# WL-AUDIO.net
KiCad netlist of a schematic drawn in Altium Designer
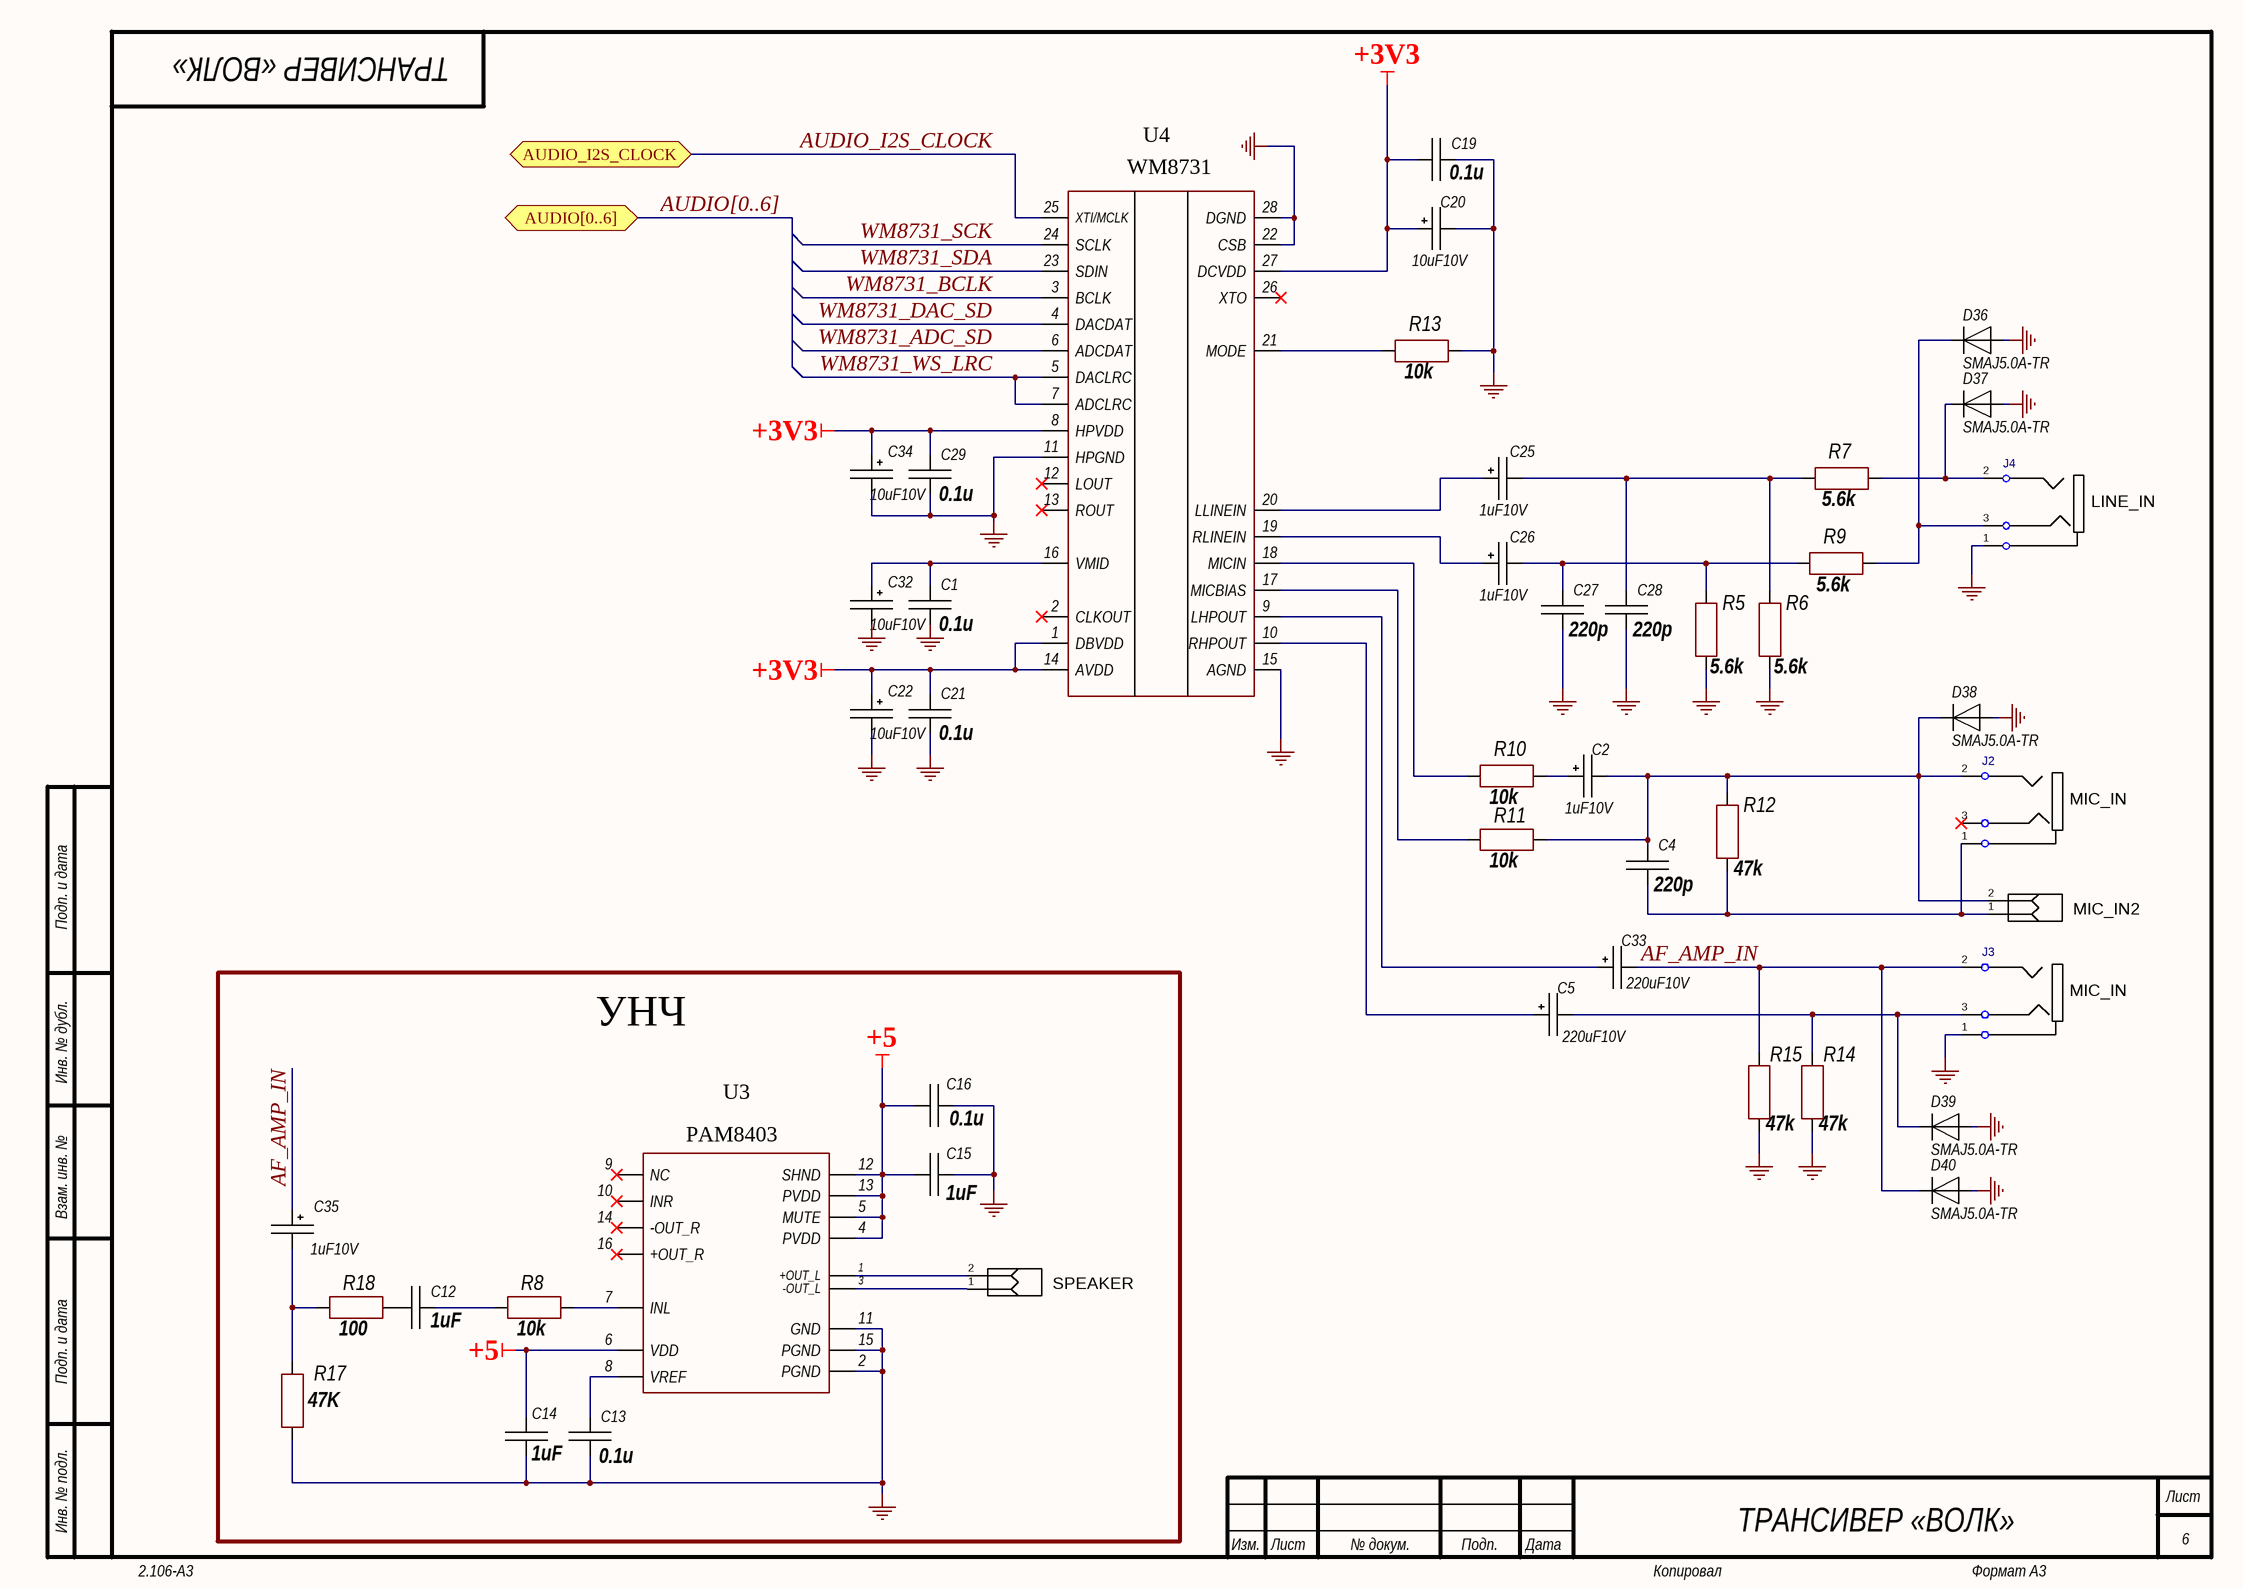
[diagram p0: WL-AUDIO.SchDoc]

(export (version "E")
  (design (tool "Eeschema 10.0.6"))
  (components
    (comp (ref "C1")
      (value "0.1u")
      (footprint "standard:CH0201C")
      (libsource (lib "Discrete") (part "Capacitor"))
    )
    (comp (ref "C2")
      (value "1uF10V")
      (footprint "standard:D5C2H11")
      (libsource (lib "Discrete") (part "AlumCap"))
    )
    (comp (ref "C4")
      (value "220p")
      (footprint "standard:CH0201C")
      (libsource (lib "Discrete") (part "Capacitor"))
    )
    (comp (ref "C5")
      (value "220uF10V")
      (footprint "standard:D5C2H11")
      (libsource (lib "Discrete") (part "AlumCap"))
    )
    (comp (ref "C12")
      (value "1uF")
      (footprint "standard:CH0201C")
      (libsource (lib "Discrete") (part "Capacitor"))
    )
    (comp (ref "C13")
      (value "0.1u")
      (footprint "standard:CH0805C")
      (libsource (lib "Discrete") (part "Capacitor"))
    )
    (comp (ref "C14")
      (value "1uF")
      (footprint "standard:CH0805C")
      (libsource (lib "Discrete") (part "Capacitor"))
    )
    (comp (ref "C15")
      (value "1uF")
      (footprint "standard:CH0805C")
      (libsource (lib "Discrete") (part "Capacitor"))
    )
    (comp (ref "C16")
      (value "0.1u")
      (footprint "standard:CH0805C")
      (libsource (lib "Discrete") (part "Capacitor"))
    )
    (comp (ref "C19")
      (value "0.1u")
      (footprint "standard:CH0201C")
      (libsource (lib "Discrete") (part "Capacitor"))
    )
    (comp (ref "C20")
      (value "10uF10V")
      (footprint "standard:D5C2H11")
      (libsource (lib "Discrete") (part "AlumCap"))
    )
    (comp (ref "C21")
      (value "0.1u")
      (footprint "standard:CH0201C")
      (libsource (lib "Discrete") (part "Capacitor"))
    )
    (comp (ref "C22")
      (value "10uF10V")
      (footprint "standard:D5C2H11")
      (libsource (lib "Discrete") (part "AlumCap"))
    )
    (comp (ref "C25")
      (value "1uF10V")
      (footprint "standard:D5C2H11")
      (libsource (lib "Discrete") (part "AlumCap"))
    )
    (comp (ref "C26")
      (value "1uF10V")
      (footprint "standard:D5C2H11")
      (libsource (lib "Discrete") (part "AlumCap"))
    )
    (comp (ref "C27")
      (value "220p")
      (footprint "standard:CH0201C")
      (libsource (lib "Discrete") (part "Capacitor"))
    )
    (comp (ref "C28")
      (value "220p")
      (footprint "standard:CH0201C")
      (libsource (lib "Discrete") (part "Capacitor"))
    )
    (comp (ref "C29")
      (value "0.1u")
      (footprint "standard:CH0201C")
      (libsource (lib "Discrete") (part "Capacitor"))
    )
    (comp (ref "C32")
      (value "10uF10V")
      (footprint "standard:D5C2H11")
      (libsource (lib "Discrete") (part "AlumCap"))
    )
    (comp (ref "C33")
      (value "220uF10V")
      (footprint "standard:D5C2H11")
      (libsource (lib "Discrete") (part "AlumCap"))
    )
    (comp (ref "C34")
      (value "10uF10V")
      (footprint "standard:D5C2H11")
      (libsource (lib "Discrete") (part "AlumCap"))
    )
    (comp (ref "C35")
      (value "1uF10V")
      (footprint "standard:D5C2H11")
      (libsource (lib "Discrete") (part "AlumCap"))
    )
    (comp (ref "D36")
      (value "SMAJ5.0A-TR")
      (footprint "standard:SOD123")
      (libsource (lib "Diods") (part "Diod"))
    )
    (comp (ref "D37")
      (value "SMAJ5.0A-TR")
      (footprint "standard:SOD123")
      (libsource (lib "Diods") (part "Diod"))
    )
    (comp (ref "D38")
      (value "SMAJ5.0A-TR")
      (footprint "standard:SOD123")
      (libsource (lib "Diods") (part "Diod"))
    )
    (comp (ref "D39")
      (value "SMAJ5.0A-TR")
      (footprint "standard:SOD123")
      (libsource (lib "Diods") (part "Diod"))
    )
    (comp (ref "D40")
      (value "SMAJ5.0A-TR")
      (footprint "standard:SOD123")
      (libsource (lib "Diods") (part "Diod"))
    )
    (comp (ref "J2")
      (value "MIC_IN")
      (footprint "SJ1-3525NG")
      (description "SJ1-3525NG")
      (libsource (lib "*") (part "SJ1-3523N"))
    )
    (comp (ref "J3")
      (value "MIC_IN")
      (footprint "SJ1-3525NG")
      (description "SJ1-3525NG")
      (libsource (lib "*") (part "SJ1-3523N"))
    )
    (comp (ref "J4")
      (value "LINE_IN")
      (footprint "SJ1-3525NG")
      (description "SJ1-3525NG")
      (libsource (lib "*") (part "SJ1-3523N"))
    )
    (comp (ref "MIС_IN2")
      (value "MIС_IN2")
      (footprint "51022-0200")
      (description "2 Pin")
      (libsource (lib "*") (part "51022-0200"))
    )
    (comp (ref "R5")
      (value "5.6k")
      (footprint "standard:CH0805R")
      (libsource (lib "Discrete") (part "Resistor"))
    )
    (comp (ref "R6")
      (value "5.6k")
      (footprint "standard:CH0805R")
      (libsource (lib "Discrete") (part "Resistor"))
    )
    (comp (ref "R7") (value "5.6k") (footprint "standard:CH0805R") (libsource (lib "") (part "Resistor_1")))
    (comp (ref "R8") (value "10k") (footprint "standard:CH0805R") (libsource (lib "") (part "Resistor_1")))
    (comp (ref "R9") (value "5.6k") (footprint "standard:CH0805R") (libsource (lib "") (part "Resistor_1")))
    (comp (ref "R10") (value "10k") (footprint "standard:CH0805R") (libsource (lib "") (part "Resistor_1")))
    (comp (ref "R11") (value "10k") (footprint "standard:CH0805R") (libsource (lib "") (part "Resistor_1")))
    (comp (ref "R12")
      (value "47k")
      (footprint "standard:CH0805R")
      (libsource (lib "Discrete") (part "Resistor"))
    )
    (comp (ref "R13") (value "10k") (footprint "standard:CH0805R") (libsource (lib "") (part "Resistor_1")))
    (comp (ref "R14")
      (value "47k")
      (footprint "standard:CH0805R")
      (libsource (lib "Discrete") (part "Resistor"))
    )
    (comp (ref "R15")
      (value "47k")
      (footprint "standard:CH0805R")
      (libsource (lib "Discrete") (part "Resistor"))
    )
    (comp (ref "R17")
      (value "47K")
      (footprint "standard:CH0805R")
      (libsource (lib "Discrete") (part "Resistor"))
    )
    (comp (ref "R18") (value "100") (footprint "standard:CH0805R") (libsource (lib "") (part "Resistor_1")))
    (comp (ref "SPEAKER")
      (value "MIС_IN2")
      (footprint "51022-0200")
      (description "2 Pin")
      (libsource (lib "*") (part "51022-0200"))
    )
    (comp (ref "U3") (value "PAM8403") (footprint "16-SOP") (libsource (lib "Digital") (part "PAM8403")))
    (comp (ref "U4") (value "WM8731") (footprint "28-SSOP") (libsource (lib "Digital") (part "WM8731")))
  )
  (nets
    (net (code "8") (name "+3V3") (class "Default")
      (node (ref "C19") (pin "1") (pinfunction "1_1") (pintype "power_in"))
      (node (ref "C20") (pin "1") (pinfunction "1_1") (pintype "power_in"))
      (node (ref "C21") (pin "2") (pinfunction "2_2") (pintype "power_in"))
      (node (ref "C22") (pin "1") (pinfunction "1_1") (pintype "power_in"))
      (node (ref "C29") (pin "2") (pinfunction "2_2") (pintype "power_in"))
      (node (ref "C34") (pin "1") (pinfunction "1_1") (pintype "power_in"))
      (node (ref "U4") (pin "1") (pinfunction "DBVDD_1") (pintype "passive"))
      (node (ref "U4") (pin "14") (pinfunction "AVDD_14") (pintype "passive"))
      (node (ref "U4") (pin "27") (pinfunction "DCVDD_27") (pintype "passive"))
      (node (ref "U4") (pin "8") (pinfunction "HPVDD_8") (pintype "passive"))
    )
    (net (code "9") (name "+5") (class "Default")
      (node (ref "C14") (pin "2") (pinfunction "2_2") (pintype "power_in"))
      (node (ref "C15") (pin "2") (pinfunction "2_2") (pintype "power_in"))
      (node (ref "C16") (pin "2") (pinfunction "2_2") (pintype "power_in"))
      (node (ref "U3") (pin "12") (pinfunction "SHND_12") (pintype "passive"))
      (node (ref "U3") (pin "13") (pinfunction "PVDD_13") (pintype "passive"))
      (node (ref "U3") (pin "4") (pinfunction "PVDD_4") (pintype "passive"))
      (node (ref "U3") (pin "5") (pinfunction "MUTE_5") (pintype "passive"))
      (node (ref "U3") (pin "6") (pinfunction "VDD_6") (pintype "passive"))
    )
    (net (code "10") (name "/AF_AMP_IN") (class "Default")
      (node (ref "C33") (pin "2") (pinfunction "2_2") (pintype "power_in"))
      (node (ref "C35") (pin "1") (pinfunction "1_1") (pintype "power_in"))
      (node (ref "D40") (pin "2") (pinfunction "2_2") (pintype "passive"))
      (node (ref "J3") (pin "2") (pinfunction "tip_2") (pintype "passive"))
      (node (ref "R15") (pin "1") (pinfunction "1_1") (pintype "passive"))
    )
    (net (code "12") (name "/AUDIO_I2S_CLOCK") (class "Default")
      (node (ref "U4") (pin "25") (pinfunction "XTI/MCLK_25") (pintype "passive"))
    )
    (net (code "13") (name "/WM8731_ADC_SD") (class "Default")
      (node (ref "U4") (pin "6") (pinfunction "ADCDAT_6") (pintype "passive"))
    )
    (net (code "14") (name "/WM8731_BCLK") (class "Default")
      (node (ref "U4") (pin "3") (pinfunction "BCLK_3") (pintype "passive"))
    )
    (net (code "15") (name "/WM8731_DAC_SD") (class "Default")
      (node (ref "U4") (pin "4") (pinfunction "DACDAT_4") (pintype "passive"))
    )
    (net (code "16") (name "/WM8731_SCK") (class "Default")
      (node (ref "U4") (pin "24") (pinfunction "SCLK_24") (pintype "passive"))
    )
    (net (code "17") (name "/WM8731_SDA") (class "Default")
      (node (ref "U4") (pin "23") (pinfunction "SDIN_23") (pintype "passive"))
    )
    (net (code "18") (name "/WM8731_WS_LRC") (class "Default")
      (node (ref "U4") (pin "5") (pinfunction "DACLRC_5") (pintype "passive"))
      (node (ref "U4") (pin "7") (pinfunction "ADCLRC_7") (pintype "passive"))
    )
    (net (code "19") (name "GND") (class "Default")
      (node (ref "C1") (pin "1") (pinfunction "1_1") (pintype "power_in"))
      (node (ref "C13") (pin "1") (pinfunction "1_1") (pintype "power_in"))
      (node (ref "C14") (pin "1") (pinfunction "1_1") (pintype "power_in"))
      (node (ref "C15") (pin "1") (pinfunction "1_1") (pintype "power_in"))
      (node (ref "C16") (pin "1") (pinfunction "1_1") (pintype "power_in"))
      (node (ref "C19") (pin "2") (pinfunction "2_2") (pintype "power_in"))
      (node (ref "C20") (pin "2") (pinfunction "2_2") (pintype "power_in"))
      (node (ref "C21") (pin "1") (pinfunction "1_1") (pintype "power_in"))
      (node (ref "C22") (pin "2") (pinfunction "2_2") (pintype "power_in"))
      (node (ref "C27") (pin "1") (pinfunction "1_1") (pintype "power_in"))
      (node (ref "C28") (pin "1") (pinfunction "1_1") (pintype "power_in"))
      (node (ref "C29") (pin "1") (pinfunction "1_1") (pintype "power_in"))
      (node (ref "C32") (pin "2") (pinfunction "2_2") (pintype "power_in"))
      (node (ref "C34") (pin "2") (pinfunction "2_2") (pintype "power_in"))
      (node (ref "D36") (pin "1") (pinfunction "1_1") (pintype "passive"))
      (node (ref "D37") (pin "1") (pinfunction "1_1") (pintype "passive"))
      (node (ref "D38") (pin "1") (pinfunction "1_1") (pintype "passive"))
      (node (ref "D39") (pin "1") (pinfunction "1_1") (pintype "passive"))
      (node (ref "D40") (pin "1") (pinfunction "1_1") (pintype "passive"))
      (node (ref "J3") (pin "1") (pinfunction "sleeve_1") (pintype "passive"))
      (node (ref "J4") (pin "1") (pinfunction "sleeve_1") (pintype "passive"))
      (node (ref "R13") (pin "1") (pinfunction "1_1") (pintype "passive"))
      (node (ref "R14") (pin "2") (pinfunction "2_2") (pintype "passive"))
      (node (ref "R15") (pin "2") (pinfunction "2_2") (pintype "passive"))
      (node (ref "R17") (pin "2") (pinfunction "2_2") (pintype "passive"))
      (node (ref "R5") (pin "2") (pinfunction "2_2") (pintype "passive"))
      (node (ref "R6") (pin "2") (pinfunction "2_2") (pintype "passive"))
      (node (ref "U3") (pin "11") (pinfunction "GND_11") (pintype "passive"))
      (node (ref "U3") (pin "15") (pinfunction "PGND_15") (pintype "passive"))
      (node (ref "U3") (pin "2") (pinfunction "PGND_2") (pintype "passive"))
      (node (ref "U4") (pin "11") (pinfunction "HPGND_11") (pintype "passive"))
      (node (ref "U4") (pin "15") (pinfunction "AGND_15") (pintype "passive"))
      (node (ref "U4") (pin "22") (pinfunction "CSB_22") (pintype "passive"))
      (node (ref "U4") (pin "28") (pinfunction "DGND_28") (pintype "passive"))
    )
    (net (code "20") (name "Net-(C2-Pad1)") (class "Default")
      (node (ref "C2") (pin "1") (pinfunction "1_1") (pintype "power_in"))
      (node (ref "R10") (pin "1") (pinfunction "1_1") (pintype "passive"))
    )
    (net (code "21") (name "Net-(C12-Pad1)") (class "Default")
      (node (ref "C12") (pin "1") (pinfunction "1_1") (pintype "power_in"))
      (node (ref "R18") (pin "1") (pinfunction "1_1") (pintype "passive"))
    )
    (net (code "22") (name "Net-(C12-Pad2)") (class "Default")
      (node (ref "C12") (pin "2") (pinfunction "2_2") (pintype "power_in"))
      (node (ref "R8") (pin "2") (pinfunction "2_2") (pintype "passive"))
    )
    (net (code "23") (name "Net-(C25-Pad2)") (class "Default")
      (node (ref "C25") (pin "2") (pinfunction "2_2") (pintype "power_in"))
      (node (ref "C28") (pin "2") (pinfunction "2_2") (pintype "power_in"))
      (node (ref "R6") (pin "1") (pinfunction "1_1") (pintype "passive"))
      (node (ref "R7") (pin "2") (pinfunction "2_2") (pintype "passive"))
    )
    (net (code "24") (name "Net-(C26-Pad2)") (class "Default")
      (node (ref "C26") (pin "2") (pinfunction "2_2") (pintype "power_in"))
      (node (ref "C27") (pin "2") (pinfunction "2_2") (pintype "power_in"))
      (node (ref "R5") (pin "1") (pinfunction "1_1") (pintype "passive"))
      (node (ref "R9") (pin "2") (pinfunction "2_2") (pintype "passive"))
    )
    (net (code "25") (name "Net-(C35-Pad2)") (class "Default")
      (node (ref "C35") (pin "2") (pinfunction "2_2") (pintype "power_in"))
      (node (ref "R17") (pin "1") (pinfunction "1_1") (pintype "passive"))
      (node (ref "R18") (pin "2") (pinfunction "2_2") (pintype "passive"))
    )
    (net (code "26") (name "Net-(J2-sleeve)") (class "Default")
      (node (ref "C4") (pin "1") (pinfunction "1_1") (pintype "power_in"))
      (node (ref "J2") (pin "1") (pinfunction "sleeve_1") (pintype "passive"))
      (node (ref "MIС_IN2") (pin "1") (pinfunction "1_1") (pintype "passive"))
      (node (ref "R12") (pin "2") (pinfunction "2_2") (pintype "passive"))
    )
    (net (code "27") (name "Net-(J2-tip)") (class "Default")
      (node (ref "C2") (pin "2") (pinfunction "2_2") (pintype "power_in"))
      (node (ref "C4") (pin "2") (pinfunction "2_2") (pintype "power_in"))
      (node (ref "D38") (pin "2") (pinfunction "2_2") (pintype "passive"))
      (node (ref "J2") (pin "2") (pinfunction "tip_2") (pintype "passive"))
      (node (ref "MIС_IN2") (pin "2") (pinfunction "2_2") (pintype "passive"))
      (node (ref "R11") (pin "1") (pinfunction "1_1") (pintype "passive"))
      (node (ref "R12") (pin "1") (pinfunction "1_1") (pintype "passive"))
    )
    (net (code "28") (name "Net-(J3-ring)") (class "Default")
      (node (ref "C5") (pin "2") (pinfunction "2_2") (pintype "power_in"))
      (node (ref "D39") (pin "2") (pinfunction "2_2") (pintype "passive"))
      (node (ref "J3") (pin "3") (pinfunction "ring_3") (pintype "passive"))
      (node (ref "R14") (pin "1") (pinfunction "1_1") (pintype "passive"))
    )
    (net (code "29") (name "Net-(J4-ring)") (class "Default")
      (node (ref "D36") (pin "2") (pinfunction "2_2") (pintype "passive"))
      (node (ref "J4") (pin "3") (pinfunction "ring_3") (pintype "passive"))
      (node (ref "R9") (pin "1") (pinfunction "1_1") (pintype "passive"))
    )
    (net (code "30") (name "Net-(J4-tip)") (class "Default")
      (node (ref "D37") (pin "2") (pinfunction "2_2") (pintype "passive"))
      (node (ref "J4") (pin "2") (pinfunction "tip_2") (pintype "passive"))
      (node (ref "R7") (pin "1") (pinfunction "1_1") (pintype "passive"))
    )
    (net (code "31") (name "Net-(U3-+OUT_L)") (class "Default")
      (node (ref "SPEAKER") (pin "2") (pinfunction "2_2") (pintype "passive"))
      (node (ref "U3") (pin "1") (pinfunction "+OUT_L_1") (pintype "passive"))
    )
    (net (code "32") (name "Net-(U3--OUT_L)") (class "Default")
      (node (ref "SPEAKER") (pin "1") (pinfunction "1_1") (pintype "passive"))
      (node (ref "U3") (pin "3") (pinfunction "-OUT_L_3") (pintype "passive"))
    )
    (net (code "33") (name "Net-(U3-INL)") (class "Default")
      (node (ref "R8") (pin "1") (pinfunction "1_1") (pintype "passive"))
      (node (ref "U3") (pin "7") (pinfunction "INL_7") (pintype "passive"))
    )
    (net (code "34") (name "Net-(U3-VREF)") (class "Default")
      (node (ref "C13") (pin "2") (pinfunction "2_2") (pintype "power_in"))
      (node (ref "U3") (pin "8") (pinfunction "VREF_8") (pintype "passive"))
    )
    (net (code "35") (name "Net-(U4-LHPOUT)") (class "Default")
      (node (ref "C33") (pin "1") (pinfunction "1_1") (pintype "power_in"))
      (node (ref "U4") (pin "9") (pinfunction "LHPOUT_9") (pintype "passive"))
    )
    (net (code "36") (name "Net-(U4-LLINEIN)") (class "Default")
      (node (ref "C25") (pin "1") (pinfunction "1_1") (pintype "power_in"))
      (node (ref "U4") (pin "20") (pinfunction "LLINEIN_20") (pintype "passive"))
    )
    (net (code "37") (name "Net-(U4-MICBIAS)") (class "Default")
      (node (ref "R11") (pin "2") (pinfunction "2_2") (pintype "passive"))
      (node (ref "U4") (pin "17") (pinfunction "MICBIAS_17") (pintype "passive"))
    )
    (net (code "38") (name "Net-(U4-MICIN)") (class "Default")
      (node (ref "R10") (pin "2") (pinfunction "2_2") (pintype "passive"))
      (node (ref "U4") (pin "18") (pinfunction "MICIN_18") (pintype "passive"))
    )
    (net (code "39") (name "Net-(U4-MODE)") (class "Default")
      (node (ref "R13") (pin "2") (pinfunction "2_2") (pintype "passive"))
      (node (ref "U4") (pin "21") (pinfunction "MODE_21") (pintype "passive"))
    )
    (net (code "40") (name "Net-(U4-RHPOUT)") (class "Default")
      (node (ref "C5") (pin "1") (pinfunction "1_1") (pintype "power_in"))
      (node (ref "U4") (pin "10") (pinfunction "RHPOUT_10") (pintype "passive"))
    )
    (net (code "41") (name "Net-(U4-RLINEIN)") (class "Default")
      (node (ref "C26") (pin "1") (pinfunction "1_1") (pintype "power_in"))
      (node (ref "U4") (pin "19") (pinfunction "RLINEIN_19") (pintype "passive"))
    )
    (net (code "42") (name "Net-(U4-VMID)") (class "Default")
      (node (ref "C1") (pin "2") (pinfunction "2_2") (pintype "power_in"))
      (node (ref "C32") (pin "1") (pinfunction "1_1") (pintype "power_in"))
      (node (ref "U4") (pin "16") (pinfunction "VMID_16") (pintype "passive"))
    )
    (net (code "43") (name "unconnected-(J2-ring-Pad3)") (class "Default")
      (node (ref "J2") (pin "3") (pinfunction "ring_3") (pintype "passive+no_connect"))
    )
    (net (code "44") (name "unconnected-(U3-+OUT_R-Pad16)") (class "Default")
      (node (ref "U3") (pin "16") (pinfunction "+OUT_R_16") (pintype "passive+no_connect"))
    )
    (net (code "45") (name "unconnected-(U3--OUT_R-Pad14)") (class "Default")
      (node (ref "U3") (pin "14") (pinfunction "-OUT_R_14") (pintype "passive+no_connect"))
    )
    (net (code "46") (name "unconnected-(U3-INR-Pad10)") (class "Default")
      (node (ref "U3") (pin "10") (pinfunction "INR_10") (pintype "passive+no_connect"))
    )
    (net (code "47") (name "unconnected-(U3-NC-Pad9)") (class "Default")
      (node (ref "U3") (pin "9") (pinfunction "NC_9") (pintype "passive+no_connect"))
    )
    (net (code "48") (name "unconnected-(U4-CLKOUT-Pad2)") (class "Default")
      (node (ref "U4") (pin "2") (pinfunction "CLKOUT_2") (pintype "passive+no_connect"))
    )
    (net (code "49") (name "unconnected-(U4-LOUT-Pad12)") (class "Default")
      (node (ref "U4") (pin "12") (pinfunction "LOUT_12") (pintype "passive+no_connect"))
    )
    (net (code "50") (name "unconnected-(U4-ROUT-Pad13)") (class "Default")
      (node (ref "U4") (pin "13") (pinfunction "ROUT_13") (pintype "passive+no_connect"))
    )
    (net (code "51") (name "unconnected-(U4-XTO-Pad26)") (class "Default")
      (node (ref "U4") (pin "26") (pinfunction "XTO_26") (pintype "passive+no_connect"))
    )
  )
)
